# M307X.net
KiCad netlist of a schematic drawn in EAGLE
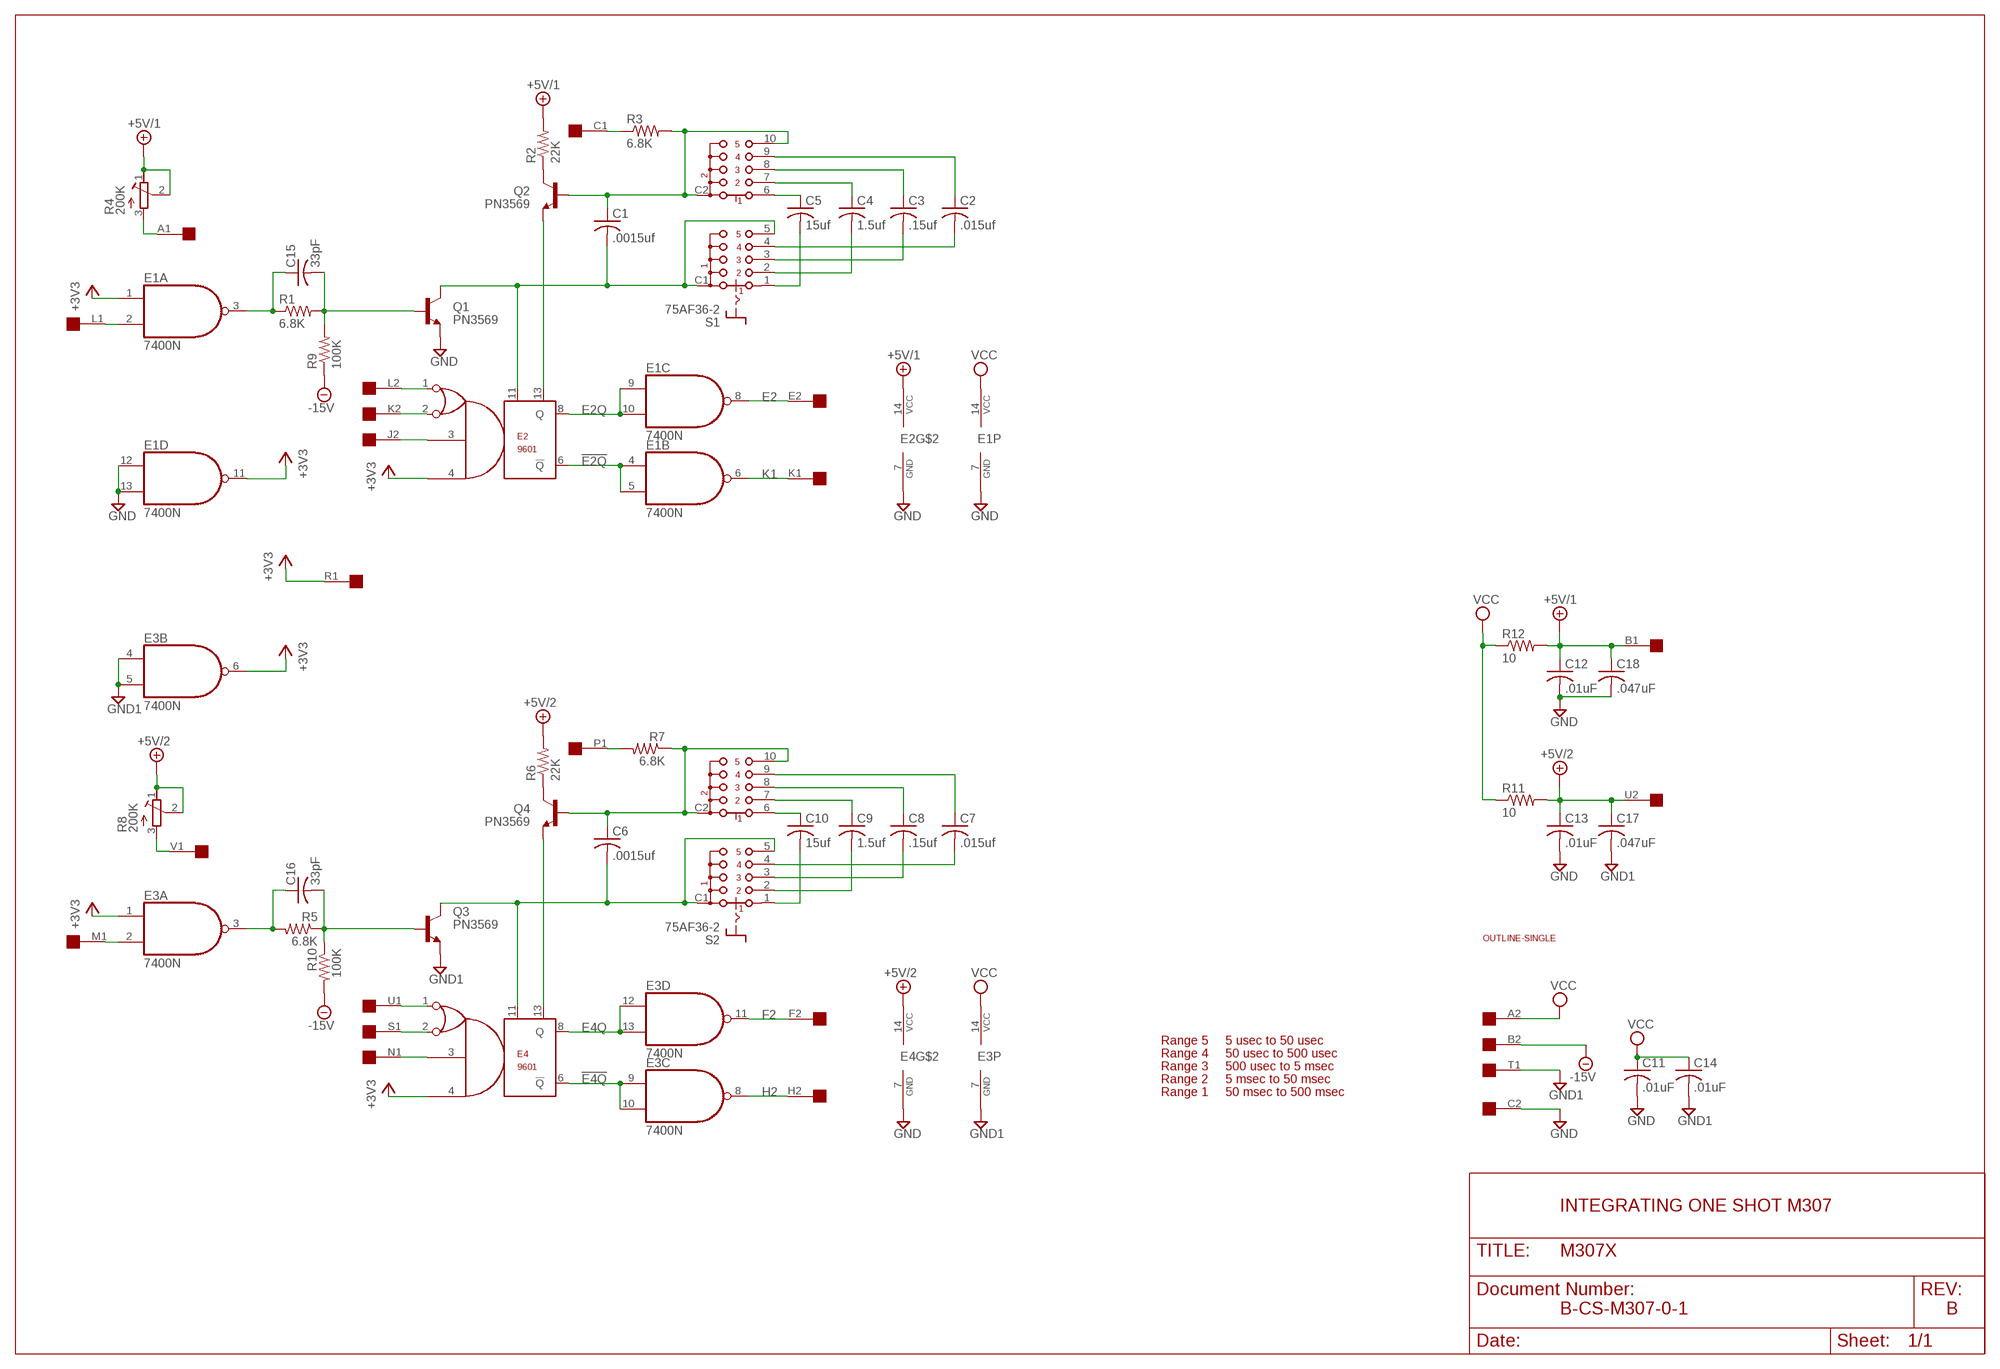
[diagram p0: schematic, sheet 1]

(export (version "E")
  (design (tool "Eeschema 10.0.6"))
  (components
    (comp (ref "C1")
      (value ".0015uf")
      (footprint "eagle-import:C050-025X075")
      (libsource (lib "eagle-import") (part "C-US050-025X075"))
    )
    (comp (ref "C2")
      (value ".015uf")
      (footprint "eagle-import:C150-054X183")
      (libsource (lib "eagle-import") (part "C-US150-054X183"))
    )
    (comp (ref "C3")
      (value ".15uf")
      (footprint "eagle-import:C150-054X183")
      (libsource (lib "eagle-import") (part "C-US150-054X183"))
    )
    (comp (ref "C4")
      (value "1.5uf")
      (footprint "eagle-import:C150-054X183")
      (libsource (lib "eagle-import") (part "C-US150-054X183"))
    )
    (comp (ref "C5")
      (value "15uf")
      (footprint "eagle-import:C150-054X183")
      (libsource (lib "eagle-import") (part "C-US150-054X183"))
    )
    (comp (ref "C6")
      (value ".0015uf")
      (footprint "eagle-import:C050-025X075")
      (libsource (lib "eagle-import") (part "C-US050-025X075"))
    )
    (comp (ref "C7")
      (value ".015uf")
      (footprint "eagle-import:C150-054X183")
      (libsource (lib "eagle-import") (part "C-US150-054X183"))
    )
    (comp (ref "C8")
      (value ".15uf")
      (footprint "eagle-import:C150-054X183")
      (libsource (lib "eagle-import") (part "C-US150-054X183"))
    )
    (comp (ref "C9")
      (value "1.5uf")
      (footprint "eagle-import:C150-054X183")
      (libsource (lib "eagle-import") (part "C-US150-054X183"))
    )
    (comp (ref "C10")
      (value "15uf")
      (footprint "eagle-import:C150-054X183")
      (libsource (lib "eagle-import") (part "C-US150-054X183"))
    )
    (comp (ref "C11")
      (value ".01uF")
      (footprint "eagle-import:C050-025X075")
      (libsource (lib "eagle-import") (part "C-US050-025X075"))
    )
    (comp (ref "C12")
      (value ".01uF")
      (footprint "eagle-import:C050-025X075")
      (libsource (lib "eagle-import") (part "C-US050-025X075"))
    )
    (comp (ref "C13")
      (value ".01uF")
      (footprint "eagle-import:C050-025X075")
      (libsource (lib "eagle-import") (part "C-US050-025X075"))
    )
    (comp (ref "C14")
      (value ".01uF")
      (footprint "eagle-import:C050-025X075")
      (libsource (lib "eagle-import") (part "C-US050-025X075"))
    )
    (comp (ref "C15")
      (value "33pF")
      (footprint "eagle-import:C050-025X075")
      (libsource (lib "eagle-import") (part "C-US050-025X075"))
    )
    (comp (ref "C16")
      (value "33pF")
      (footprint "eagle-import:C050-025X075")
      (libsource (lib "eagle-import") (part "C-US050-025X075"))
    )
    (comp (ref "C17")
      (value ".047uF")
      (footprint "eagle-import:C050-025X075")
      (libsource (lib "eagle-import") (part "C-US050-025X075"))
    )
    (comp (ref "C18")
      (value ".047uF")
      (footprint "eagle-import:C050-025X075")
      (libsource (lib "eagle-import") (part "C-US050-025X075"))
    )
    (comp (ref "E1")
      (value "7400N")
      (footprint "eagle-import:DIL14")
      (libsource (lib "eagle-import") (part "7400N"))
    )
    (comp (ref "E2")
      (value "9601")
      (footprint "eagle-import:DIL14")
      (libsource (lib "eagle-import") (part "9601"))
    )
    (comp (ref "E3")
      (value "7400N")
      (footprint "eagle-import:DIL14")
      (libsource (lib "eagle-import") (part "7400N"))
    )
    (comp (ref "E4")
      (value "9601")
      (footprint "eagle-import:DIL14")
      (libsource (lib "eagle-import") (part "9601"))
    )
    (comp (ref "Q1")
      (value "PN3569")
      (footprint "eagle-import:TO39")
      (libsource (lib "eagle-import") (part "-NPN-TO39-EBC2N3019"))
    )
    (comp (ref "Q2")
      (value "PN3569")
      (footprint "eagle-import:TO39")
      (libsource (lib "eagle-import") (part "-NPN-TO39-EBC2N3019"))
    )
    (comp (ref "Q3")
      (value "PN3569")
      (footprint "eagle-import:TO39")
      (libsource (lib "eagle-import") (part "-NPN-TO39-EBC2N3019"))
    )
    (comp (ref "Q4")
      (value "PN3569")
      (footprint "eagle-import:TO39")
      (libsource (lib "eagle-import") (part "-NPN-TO39-EBC2N3019"))
    )
    (comp (ref "R1")
      (value "6.8K")
      (footprint "eagle-import:0207_10")
      (libsource (lib "eagle-import") (part "R-US_0207/10"))
    )
    (comp (ref "R2")
      (value "22K")
      (footprint "eagle-import:0207_10")
      (libsource (lib "eagle-import") (part "R-US_0207/10"))
    )
    (comp (ref "R3")
      (value "6.8K")
      (footprint "eagle-import:0207_10")
      (libsource (lib "eagle-import") (part "R-US_0207/10"))
    )
    (comp (ref "R4")
      (value "200K")
      (footprint "eagle-import:3006Y")
      (libsource (lib "eagle-import") (part "275P"))
    )
    (comp (ref "R5")
      (value "6.8K")
      (footprint "eagle-import:0207_10")
      (libsource (lib "eagle-import") (part "R-US_0207/10"))
    )
    (comp (ref "R6")
      (value "22K")
      (footprint "eagle-import:0207_10")
      (libsource (lib "eagle-import") (part "R-US_0207/10"))
    )
    (comp (ref "R7")
      (value "6.8K")
      (footprint "eagle-import:0207_10")
      (libsource (lib "eagle-import") (part "R-US_0207/10"))
    )
    (comp (ref "R8")
      (value "200K")
      (footprint "eagle-import:3006Y")
      (libsource (lib "eagle-import") (part "275P"))
    )
    (comp (ref "R9")
      (value "100K")
      (footprint "eagle-import:0207_10")
      (libsource (lib "eagle-import") (part "R-US_0207/10"))
    )
    (comp (ref "R10")
      (value "100K")
      (footprint "eagle-import:0207_10")
      (libsource (lib "eagle-import") (part "R-US_0207/10"))
    )
    (comp (ref "R11")
      (value "10")
      (footprint "eagle-import:0207_10")
      (libsource (lib "eagle-import") (part "R-US_0207/10"))
    )
    (comp (ref "R12")
      (value "10")
      (footprint "eagle-import:0207_10")
      (libsource (lib "eagle-import") (part "R-US_0207/10"))
    )
    (comp (ref "S1")
      (value "75AF36-2")
      (footprint "eagle-import:75AF36-2")
      (libsource (lib "eagle-import") (part "75?36-2AF"))
    )
    (comp (ref "S2")
      (value "75AF36-2")
      (footprint "eagle-import:75AF36-2")
      (libsource (lib "eagle-import") (part "75?36-2AF"))
    )
    (comp (ref "U$1")
      (value "OUTLINE-SINGLE")
      (footprint "eagle-import:SINGLE")
      (libsource (lib "eagle-import") (part "OUTLINE-SINGLE"))
    )
    (comp (ref "U$4")
      (value "SINGLE")
      (footprint "eagle-import:EDGE-CON2")
      (libsource (lib "eagle-import") (part "SINGLE"))
    )
  )
  (nets
    (net (code "1") (name "+3V3") (class "Default")
      (node (ref "E1") (pin "1") (pinfunction "I0_1") (pintype "input"))
      (node (ref "E1") (pin "11") (pinfunction "O_11") (pintype "output"))
      (node (ref "E2") (pin "4") (pinfunction "P$4_4") (pintype "input"))
      (node (ref "E3") (pin "1") (pinfunction "I0_1") (pintype "input"))
      (node (ref "E3") (pin "6") (pinfunction "O_6") (pintype "output"))
      (node (ref "E4") (pin "4") (pinfunction "P$4_4") (pintype "input"))
      (node (ref "U$4") (pin "R1") (pinfunction "1_R1") (pintype "bidirectional"))
    )
    (net (code "2") (name "+5V{slash}1") (class "Default")
      (node (ref "C12") (pin "1") (pinfunction "1_1") (pintype "passive"))
      (node (ref "C18") (pin "1") (pinfunction "1_1") (pintype "passive"))
      (node (ref "E2") (pin "14") (pinfunction "VCC_14") (pintype "power_in"))
      (node (ref "R12") (pin "2") (pinfunction "2_2") (pintype "passive"))
      (node (ref "R2") (pin "2") (pinfunction "2_2") (pintype "passive"))
      (node (ref "R4") (pin "1") (pinfunction "A_1") (pintype "passive"))
      (node (ref "R4") (pin "2") (pinfunction "S_2") (pintype "passive"))
      (node (ref "U$4") (pin "B1") (pinfunction "1_B1") (pintype "bidirectional"))
    )
    (net (code "3") (name "+5V{slash}2") (class "Default")
      (node (ref "C13") (pin "1") (pinfunction "1_1") (pintype "passive"))
      (node (ref "C17") (pin "1") (pinfunction "1_1") (pintype "passive"))
      (node (ref "E4") (pin "14") (pinfunction "VCC_14") (pintype "power_in"))
      (node (ref "R11") (pin "2") (pinfunction "2_2") (pintype "passive"))
      (node (ref "R6") (pin "2") (pinfunction "2_2") (pintype "passive"))
      (node (ref "R8") (pin "1") (pinfunction "A_1") (pintype "passive"))
      (node (ref "R8") (pin "2") (pinfunction "S_2") (pintype "passive"))
      (node (ref "U$4") (pin "U2") (pinfunction "1_U2") (pintype "bidirectional"))
    )
    (net (code "4") (name "-15V") (class "Default")
      (node (ref "R10") (pin "2") (pinfunction "2_2") (pintype "passive"))
      (node (ref "R9") (pin "1") (pinfunction "1_1") (pintype "passive"))
      (node (ref "U$4") (pin "B2") (pinfunction "1_B2") (pintype "bidirectional"))
    )
    (net (code "5") (name "/E2") (class "Default")
      (node (ref "E1") (pin "8") (pinfunction "O_8") (pintype "output"))
      (node (ref "U$4") (pin "E2") (pinfunction "1_E2") (pintype "bidirectional"))
    )
    (net (code "6") (name "/E2Q") (class "Default")
      (node (ref "E1") (pin "10") (pinfunction "I1_10") (pintype "input"))
      (node (ref "E1") (pin "9") (pinfunction "I0_9") (pintype "input"))
      (node (ref "E2") (pin "8") (pinfunction "Q_8") (pintype "output"))
    )
    (net (code "7") (name "/E4Q") (class "Default")
      (node (ref "E3") (pin "12") (pinfunction "I0_12") (pintype "input"))
      (node (ref "E3") (pin "13") (pinfunction "I1_13") (pintype "input"))
      (node (ref "E4") (pin "8") (pinfunction "Q_8") (pintype "output"))
    )
    (net (code "8") (name "/F2") (class "Default")
      (node (ref "E3") (pin "11") (pinfunction "O_11") (pintype "output"))
      (node (ref "U$4") (pin "F2") (pinfunction "1_F2") (pintype "bidirectional"))
    )
    (net (code "9") (name "/H2") (class "Default")
      (node (ref "E3") (pin "8") (pinfunction "O_8") (pintype "output"))
      (node (ref "U$4") (pin "H2") (pinfunction "1_H2") (pintype "bidirectional"))
    )
    (net (code "10") (name "/K1") (class "Default")
      (node (ref "E1") (pin "6") (pinfunction "O_6") (pintype "output"))
      (node (ref "U$4") (pin "K1") (pinfunction "1_K1") (pintype "bidirectional"))
    )
    (net (code "11") (name "/~{E2Q}") (class "Default")
      (node (ref "E1") (pin "4") (pinfunction "I0_4") (pintype "input"))
      (node (ref "E1") (pin "5") (pinfunction "I1_5") (pintype "input"))
      (node (ref "E2") (pin "6") (pinfunction "~{Q}_6") (pintype "output"))
    )
    (net (code "12") (name "/~{E4Q}") (class "Default")
      (node (ref "E3") (pin "10") (pinfunction "I1_10") (pintype "input"))
      (node (ref "E3") (pin "9") (pinfunction "I0_9") (pintype "input"))
      (node (ref "E4") (pin "6") (pinfunction "~{Q}_6") (pintype "output"))
    )
    (net (code "13") (name "GND") (class "Default")
      (node (ref "C11") (pin "2") (pinfunction "2_2") (pintype "passive"))
      (node (ref "C12") (pin "2") (pinfunction "2_2") (pintype "passive"))
      (node (ref "C13") (pin "2") (pinfunction "2_2") (pintype "passive"))
      (node (ref "C18") (pin "2") (pinfunction "2_2") (pintype "passive"))
      (node (ref "E1") (pin "12") (pinfunction "I0_12") (pintype "input"))
      (node (ref "E1") (pin "13") (pinfunction "I1_13") (pintype "input"))
      (node (ref "E1") (pin "7") (pinfunction "GND_7") (pintype "power_in"))
      (node (ref "E2") (pin "7") (pinfunction "GND_7") (pintype "power_in"))
      (node (ref "E4") (pin "7") (pinfunction "GND_7") (pintype "power_in"))
      (node (ref "Q1") (pin "1") (pinfunction "E_1") (pintype "passive"))
      (node (ref "U$4") (pin "C2") (pinfunction "1_C2") (pintype "bidirectional"))
    )
    (net (code "14") (name "GND1") (class "Default")
      (node (ref "C14") (pin "2") (pinfunction "2_2") (pintype "passive"))
      (node (ref "C17") (pin "2") (pinfunction "2_2") (pintype "passive"))
      (node (ref "E3") (pin "4") (pinfunction "I0_4") (pintype "input"))
      (node (ref "E3") (pin "5") (pinfunction "I1_5") (pintype "input"))
      (node (ref "E3") (pin "7") (pinfunction "GND_7") (pintype "power_in"))
      (node (ref "Q3") (pin "1") (pinfunction "E_1") (pintype "passive"))
      (node (ref "U$4") (pin "T1") (pinfunction "1_T1") (pintype "bidirectional"))
    )
    (net (code "15") (name "Net-(E1A-I1)") (class "Default")
      (node (ref "E1") (pin "2") (pinfunction "I1_2") (pintype "input"))
      (node (ref "U$4") (pin "L1") (pinfunction "1_L1") (pintype "bidirectional"))
    )
    (net (code "16") (name "Net-(E1A-O)") (class "Default")
      (node (ref "C15") (pin "1") (pinfunction "1_1") (pintype "passive"))
      (node (ref "E1") (pin "3") (pinfunction "O_3") (pintype "output"))
      (node (ref "R1") (pin "1") (pinfunction "1_1") (pintype "passive"))
    )
    (net (code "17") (name "Net-(E2A-P$1)") (class "Default")
      (node (ref "E2") (pin "1") (pinfunction "P$1_1") (pintype "input"))
      (node (ref "U$4") (pin "L2") (pinfunction "1_L2") (pintype "bidirectional"))
    )
    (net (code "18") (name "Net-(E2A-P$2)") (class "Default")
      (node (ref "E2") (pin "2") (pinfunction "P$2_2") (pintype "input"))
      (node (ref "U$4") (pin "K2") (pinfunction "1_K2") (pintype "bidirectional"))
    )
    (net (code "19") (name "Net-(E2A-P$3)") (class "Default")
      (node (ref "E2") (pin "3") (pinfunction "P$3_3") (pintype "input"))
      (node (ref "U$4") (pin "J2") (pinfunction "1_J2") (pintype "bidirectional"))
    )
    (net (code "20") (name "Net-(E2A-P$5)") (class "Default")
      (node (ref "C1") (pin "2") (pinfunction "2_2") (pintype "passive"))
      (node (ref "E2") (pin "11") (pinfunction "P$5_11") (pintype "bidirectional"))
      (node (ref "Q1") (pin "3") (pinfunction "C_3") (pintype "passive"))
      (node (ref "S1") (pin "5") (pinfunction "51_5") (pintype "passive"))
      (node (ref "S1") (pin "C1") (pinfunction "C1_C1") (pintype "passive"))
    )
    (net (code "21") (name "Net-(E2A-P$6)") (class "Default")
      (node (ref "E2") (pin "13") (pinfunction "P$6_13") (pintype "bidirectional"))
      (node (ref "Q2") (pin "1") (pinfunction "E_1") (pintype "passive"))
    )
    (net (code "22") (name "Net-(E3A-I1)") (class "Default")
      (node (ref "E3") (pin "2") (pinfunction "I1_2") (pintype "input"))
      (node (ref "U$4") (pin "M1") (pinfunction "1_M1") (pintype "bidirectional"))
    )
    (net (code "23") (name "Net-(E3A-O)") (class "Default")
      (node (ref "C16") (pin "1") (pinfunction "1_1") (pintype "passive"))
      (node (ref "E3") (pin "3") (pinfunction "O_3") (pintype "output"))
      (node (ref "R5") (pin "2") (pinfunction "2_2") (pintype "passive"))
    )
    (net (code "24") (name "Net-(E4A-P$1)") (class "Default")
      (node (ref "E4") (pin "1") (pinfunction "P$1_1") (pintype "input"))
      (node (ref "U$4") (pin "U1") (pinfunction "1_U1") (pintype "bidirectional"))
    )
    (net (code "25") (name "Net-(E4A-P$2)") (class "Default")
      (node (ref "E4") (pin "2") (pinfunction "P$2_2") (pintype "input"))
      (node (ref "U$4") (pin "S1") (pinfunction "1_S1") (pintype "bidirectional"))
    )
    (net (code "26") (name "Net-(E4A-P$3)") (class "Default")
      (node (ref "E4") (pin "3") (pinfunction "P$3_3") (pintype "input"))
      (node (ref "U$4") (pin "N1") (pinfunction "1_N1") (pintype "bidirectional"))
    )
    (net (code "27") (name "Net-(E4A-P$5)") (class "Default")
      (node (ref "C6") (pin "2") (pinfunction "2_2") (pintype "passive"))
      (node (ref "E4") (pin "11") (pinfunction "P$5_11") (pintype "bidirectional"))
      (node (ref "Q3") (pin "3") (pinfunction "C_3") (pintype "passive"))
      (node (ref "S2") (pin "5") (pinfunction "51_5") (pintype "passive"))
      (node (ref "S2") (pin "C1") (pinfunction "C1_C1") (pintype "passive"))
    )
    (net (code "28") (name "Net-(E4A-P$6)") (class "Default")
      (node (ref "E4") (pin "13") (pinfunction "P$6_13") (pintype "bidirectional"))
      (node (ref "Q4") (pin "1") (pinfunction "E_1") (pintype "passive"))
    )
    (net (code "29") (name "Net-(Q1-B)") (class "Default")
      (node (ref "C15") (pin "2") (pinfunction "2_2") (pintype "passive"))
      (node (ref "Q1") (pin "2") (pinfunction "B_2") (pintype "passive"))
      (node (ref "R1") (pin "2") (pinfunction "2_2") (pintype "passive"))
      (node (ref "R9") (pin "2") (pinfunction "2_2") (pintype "passive"))
    )
    (net (code "30") (name "Net-(Q2-B)") (class "Default")
      (node (ref "C1") (pin "1") (pinfunction "1_1") (pintype "passive"))
      (node (ref "Q2") (pin "2") (pinfunction "B_2") (pintype "passive"))
      (node (ref "R3") (pin "2") (pinfunction "2_2") (pintype "passive"))
      (node (ref "S1") (pin "10") (pinfunction "52_10") (pintype "passive"))
      (node (ref "S1") (pin "C2") (pinfunction "C2_C2") (pintype "passive"))
    )
    (net (code "31") (name "Net-(Q2-C)") (class "Default")
      (node (ref "Q2") (pin "3") (pinfunction "C_3") (pintype "passive"))
      (node (ref "R2") (pin "1") (pinfunction "1_1") (pintype "passive"))
    )
    (net (code "32") (name "Net-(Q3-B)") (class "Default")
      (node (ref "C16") (pin "2") (pinfunction "2_2") (pintype "passive"))
      (node (ref "Q3") (pin "2") (pinfunction "B_2") (pintype "passive"))
      (node (ref "R10") (pin "1") (pinfunction "1_1") (pintype "passive"))
      (node (ref "R5") (pin "1") (pinfunction "1_1") (pintype "passive"))
    )
    (net (code "33") (name "Net-(Q4-B)") (class "Default")
      (node (ref "C6") (pin "1") (pinfunction "1_1") (pintype "passive"))
      (node (ref "Q4") (pin "2") (pinfunction "B_2") (pintype "passive"))
      (node (ref "R7") (pin "1") (pinfunction "1_1") (pintype "passive"))
      (node (ref "S2") (pin "10") (pinfunction "52_10") (pintype "passive"))
      (node (ref "S2") (pin "C2") (pinfunction "C2_C2") (pintype "passive"))
    )
    (net (code "34") (name "Net-(Q4-C)") (class "Default")
      (node (ref "Q4") (pin "3") (pinfunction "C_3") (pintype "passive"))
      (node (ref "R6") (pin "1") (pinfunction "1_1") (pintype "passive"))
    )
    (net (code "35") (name "Net-(R4-E)") (class "Default")
      (node (ref "R4") (pin "3") (pinfunction "E_3") (pintype "passive"))
      (node (ref "U$4") (pin "A1") (pinfunction "1_A1") (pintype "bidirectional"))
    )
    (net (code "36") (name "Net-(R8-E)") (class "Default")
      (node (ref "R8") (pin "3") (pinfunction "E_3") (pintype "passive"))
      (node (ref "U$4") (pin "V1") (pinfunction "1_V1") (pintype "bidirectional"))
    )
    (net (code "37") (name "Net-(S1-11)") (class "Default")
      (node (ref "C5") (pin "2") (pinfunction "2_2") (pintype "passive"))
      (node (ref "S1") (pin "1") (pinfunction "11_1") (pintype "passive"))
    )
    (net (code "38") (name "Net-(S1-12)") (class "Default")
      (node (ref "C5") (pin "1") (pinfunction "1_1") (pintype "passive"))
      (node (ref "S1") (pin "6") (pinfunction "12_6") (pintype "passive"))
    )
    (net (code "39") (name "Net-(S1-21)") (class "Default")
      (node (ref "C4") (pin "2") (pinfunction "2_2") (pintype "passive"))
      (node (ref "S1") (pin "2") (pinfunction "21_2") (pintype "passive"))
    )
    (net (code "40") (name "Net-(S1-22)") (class "Default")
      (node (ref "C4") (pin "1") (pinfunction "1_1") (pintype "passive"))
      (node (ref "S1") (pin "7") (pinfunction "22_7") (pintype "passive"))
    )
    (net (code "41") (name "Net-(S1-31)") (class "Default")
      (node (ref "C3") (pin "2") (pinfunction "2_2") (pintype "passive"))
      (node (ref "S1") (pin "3") (pinfunction "31_3") (pintype "passive"))
    )
    (net (code "42") (name "Net-(S1-32)") (class "Default")
      (node (ref "C3") (pin "1") (pinfunction "1_1") (pintype "passive"))
      (node (ref "S1") (pin "8") (pinfunction "32_8") (pintype "passive"))
    )
    (net (code "43") (name "Net-(S1-41)") (class "Default")
      (node (ref "C2") (pin "2") (pinfunction "2_2") (pintype "passive"))
      (node (ref "S1") (pin "4") (pinfunction "41_4") (pintype "passive"))
    )
    (net (code "44") (name "Net-(S1-42)") (class "Default")
      (node (ref "C2") (pin "1") (pinfunction "1_1") (pintype "passive"))
      (node (ref "S1") (pin "9") (pinfunction "42_9") (pintype "passive"))
    )
    (net (code "45") (name "Net-(S2-11)") (class "Default")
      (node (ref "C10") (pin "2") (pinfunction "2_2") (pintype "passive"))
      (node (ref "S2") (pin "1") (pinfunction "11_1") (pintype "passive"))
    )
    (net (code "46") (name "Net-(S2-12)") (class "Default")
      (node (ref "C10") (pin "1") (pinfunction "1_1") (pintype "passive"))
      (node (ref "S2") (pin "6") (pinfunction "12_6") (pintype "passive"))
    )
    (net (code "47") (name "Net-(S2-21)") (class "Default")
      (node (ref "C9") (pin "2") (pinfunction "2_2") (pintype "passive"))
      (node (ref "S2") (pin "2") (pinfunction "21_2") (pintype "passive"))
    )
    (net (code "48") (name "Net-(S2-22)") (class "Default")
      (node (ref "C9") (pin "1") (pinfunction "1_1") (pintype "passive"))
      (node (ref "S2") (pin "7") (pinfunction "22_7") (pintype "passive"))
    )
    (net (code "49") (name "Net-(S2-31)") (class "Default")
      (node (ref "C8") (pin "2") (pinfunction "2_2") (pintype "passive"))
      (node (ref "S2") (pin "3") (pinfunction "31_3") (pintype "passive"))
    )
    (net (code "50") (name "Net-(S2-32)") (class "Default")
      (node (ref "C8") (pin "1") (pinfunction "1_1") (pintype "passive"))
      (node (ref "S2") (pin "8") (pinfunction "32_8") (pintype "passive"))
    )
    (net (code "51") (name "Net-(S2-41)") (class "Default")
      (node (ref "C7") (pin "2") (pinfunction "2_2") (pintype "passive"))
      (node (ref "S2") (pin "4") (pinfunction "41_4") (pintype "passive"))
    )
    (net (code "52") (name "Net-(S2-42)") (class "Default")
      (node (ref "C7") (pin "1") (pinfunction "1_1") (pintype "passive"))
      (node (ref "S2") (pin "9") (pinfunction "42_9") (pintype "passive"))
    )
    (net (code "53") (name "Net-(U$4E-1)") (class "Default")
      (node (ref "R3") (pin "1") (pinfunction "1_1") (pintype "passive"))
      (node (ref "U$4") (pin "C1") (pinfunction "1_C1") (pintype "bidirectional"))
    )
    (net (code "54") (name "Net-(U$4Y-1)") (class "Default")
      (node (ref "R7") (pin "2") (pinfunction "2_2") (pintype "passive"))
      (node (ref "U$4") (pin "P1") (pinfunction "1_P1") (pintype "bidirectional"))
    )
    (net (code "55") (name "VCC") (class "Default")
      (node (ref "C11") (pin "1") (pinfunction "1_1") (pintype "passive"))
      (node (ref "C14") (pin "1") (pinfunction "1_1") (pintype "passive"))
      (node (ref "E1") (pin "14") (pinfunction "VCC_14") (pintype "power_in"))
      (node (ref "E3") (pin "14") (pinfunction "VCC_14") (pintype "power_in"))
      (node (ref "R11") (pin "1") (pinfunction "1_1") (pintype "passive"))
      (node (ref "R12") (pin "1") (pinfunction "1_1") (pintype "passive"))
      (node (ref "U$4") (pin "A2") (pinfunction "1_A2") (pintype "bidirectional"))
    )
  )
)
